# Charging.net
KiCad netlist of a schematic drawn in Altium Designer
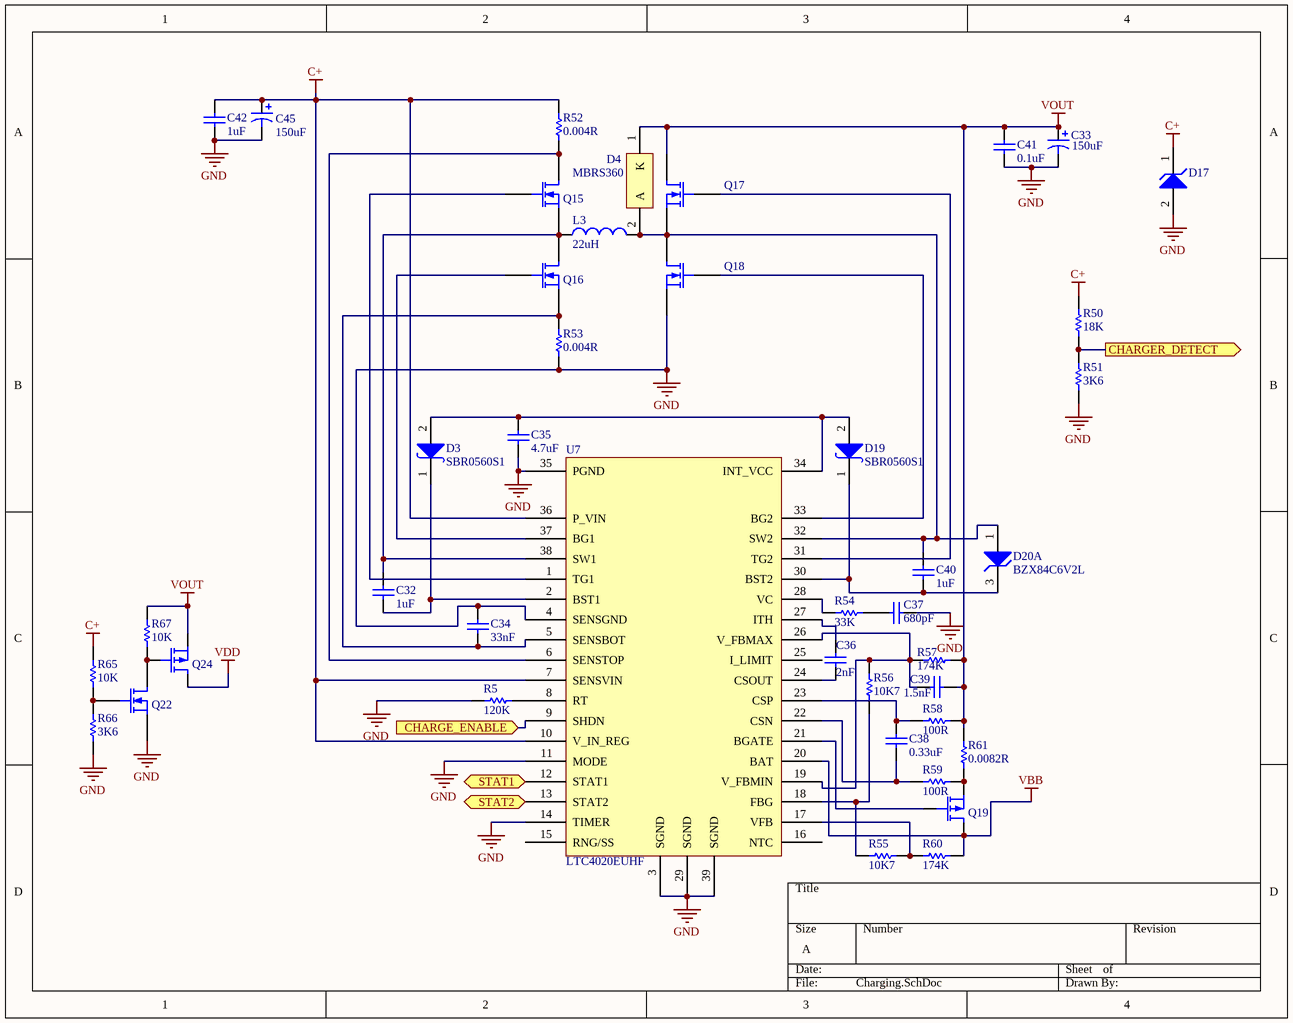
[diagram p0: Charging.SchDoc]

(export (version "E")
  (design (tool "Eeschema 10.0.6"))
  (components
    (comp (ref "C32")
      (value "1uF")
      (footprint "CAPC0603(1608)100_L")
      (description "CAP 1uF 25V Â±10% 0603 (1608 Metric) Thickness 1mm SMD")
      (fields (field (name "TOLERANCE") "Â±10%"))
      (libsource (lib "Altium Content Vault") (part "CAP"))
    )
    (comp (ref "C33")
      (value "150uF")
      (footprint "CAP 180uF 50V")
      (description "Polarized Capacitor (Axial)")
      (fields (field (name "PUBLISHER") "Altium Limited"))
      (libsource (lib "Components") (part "CAP 180uF 50V"))
    )
    (comp (ref "C34")
      (value "33nF")
      (footprint "CAPC0603(1608)100_M")
      (description "CAP 33nF 25V Â±5% 0603 (1608 Metric) Thickness 1mm SMD")
      (fields (field (name "TOLERANCE") "Â±5%"))
      (libsource (lib "Altium Content Vault") (part "CAP"))
    )
    (comp (ref "C35")
      (value "4.7uF")
      (footprint "CAPC0603(1608)55_L")
      (description "CAP 4.7uF 6.3V Â±10% 0603 (1608 Metric) Thickness 0.55mm SMD")
      (fields (field (name "TOLERANCE") "Â±10%"))
      (libsource (lib "Altium Content Vault") (part "CMP-1035-02779-1"))
    )
    (comp (ref "C36")
      (value "2nF")
      (footprint "CAPC0603(1608)100_L")
      (description "CAP 2.2nF 6.3V Â±5% 0603 (1608 Metric) Thickness 1mm SMD")
      (fields (field (name "TOLERANCE") "Â±5%"))
      (libsource (lib "Altium Content Vault") (part "CAP"))
    )
    (comp (ref "C37")
      (value "680pF")
      (footprint "CAPC0603(1608)100_L")
      (description "CAP 680pF 6.3V Â±5% 0603 (1608 Metric) Thickness 1mm SMD")
      (fields (field (name "TOLERANCE") "Â±5%"))
      (libsource (lib "Altium Content Vault") (part "CAP"))
    )
    (comp (ref "C38")
      (value "0.33uF")
      (footprint "CAPC0603(1608)100_M")
      (description "CAP 330nF 50V Â±10% 0603 (1608 Metric) Thickness 1mm SMD")
      (fields (field (name "TOLERANCE") "Â±10%"))
      (libsource (lib "Altium Content Vault") (part "CAP"))
    )
    (comp (ref "C39")
      (value "1.5nF")
      (footprint "CAPC0603(1608)100_N")
      (description "CAP 1.5nF 6.3V Â±5% 0603 (1608 Metric) Thickness 1mm SMD")
      (fields (field (name "TOLERANCE") "Â±5%"))
      (libsource (lib "Altium Content Vault") (part "CAP"))
    )
    (comp (ref "C40")
      (value "1uF")
      (footprint "CAPC0603(1608)100_L")
      (description "CAP 1uF 25V Â±10% 0603 (1608 Metric) Thickness 1mm SMD")
      (fields (field (name "TOLERANCE") "Â±10%"))
      (libsource (lib "Altium Content Vault") (part "CAP"))
    )
    (comp (ref "C41")
      (value "0.1uF")
      (footprint "CAPC0603(1608)100_L")
      (description "CAP 100nF 50V Â±5% 0603 (1608 Metric) Thickness 1mm SMD")
      (fields (field (name "TOLERANCE") "Â±5%"))
      (libsource (lib "Altium Content Vault") (part "CMP-1035-02591-1"))
    )
    (comp (ref "C42")
      (value "1uF")
      (footprint "CAPC0603(1608)100_L")
      (description "CAP 1uF 25V Â±10% 0603 (1608 Metric) Thickness 1mm SMD")
      (fields (field (name "TOLERANCE") "Â±10%"))
      (libsource (lib "Altium Content Vault") (part "CAP"))
    )
    (comp (ref "C45")
      (value "150uF")
      (footprint "CAP 150uF 25V")
      (description "Polarized Capacitor (Axial)")
      (fields (field (name "PUBLISHER") "Altium Limited"))
      (libsource (lib "Components") (part "CAP 150uF 25V"))
    )
    (comp (ref "D3")
      (value "SBR0560S1")
      (footprint "SOD-123")
      (libsource (lib "Components") (part "SBR0560S1"))
    )
    (comp (ref "D4")
      (value "MBRS360")
      (footprint "ONSC-SMB-2-403A-03_H_V")
      (description "Schottky Power Rectifier, 2-Pin SMB, Pb-Free, Tape and Reel")
      (fields (field (name "MANUFACTURER") "On Semiconductor") (field (name "PARTNUMBER") "MBRS360BT3G"))
      (libsource (lib "Altium Content Vault") (part "ONSC-D-K1A2-2_A"))
    )
    (comp (ref "D17")
      (value "~")
      (footprint "ONSC-SOD-123-2-425-04_V")
      (description "Zener Voltage Regulator, 500 mW, 2-Pin SOD-123, Pb-Free, Tape and Reel")
      (fields (field (name "PARTNUMBER") "MMSZ24T1G") (field (name "MANUFACTURER") "On Semiconductor"))
      (libsource (lib "Altium Inc") (part "ONSC-K1A2-2"))
    )
    (comp (ref "D19")
      (value "SBR0560S1")
      (footprint "SOD-123")
      (libsource (lib "Components") (part "SBR0560S1"))
    )
    (comp (ref "D20")
      (value "BZX84C6V2L")
      (footprint "ONSC-SOT-23-3-318-08_V")
      (description "Zener Voltage Regulator, 225 mW, 3-Pin SOT-23, Pb-Free, Tape and Reel")
      (fields (field (name "MANUFACTURER") "On Semiconductor") (field (name "PARTNUMBER") "BZX84C6V2LT3G"))
      (libsource (lib "Altium Content Vault") (part "CMP-1060-00911-1"))
    )
    (comp (ref "L3")
      (value "22uH")
      (footprint "IHLP-6767GZ")
      (description "Inductor")
      (fields (field (name "PUBLISHER") "Altium Limited"))
      (libsource (lib "Components") (part "IHLP6767"))
    )
    (comp (ref "Q15")
      (value "MOSFET-N")
      (footprint "SOIC127P600X175-8N")
      (description "N-Channel MOSFET")
      (fields (field (name "PUBLISHER") "Altium Limited"))
      (libsource (lib "Components") (part "MOSFET-N"))
    )
    (comp (ref "Q16")
      (value "MOSFET-N")
      (footprint "SOIC127P600X175-8N")
      (description "N-Channel MOSFET")
      (fields (field (name "PUBLISHER") "Altium Limited"))
      (libsource (lib "Components") (part "MOSFET-N"))
    )
    (comp (ref "Q17")
      (value "MOSFET-N")
      (footprint "SOIC127P600X175-8N")
      (description "N-Channel MOSFET")
      (fields (field (name "PUBLISHER") "Altium Limited"))
      (libsource (lib "Components") (part "MOSFET-N"))
    )
    (comp (ref "Q18")
      (value "MOSFET-N")
      (footprint "SOIC127P600X175-8N")
      (description "N-Channel MOSFET")
      (fields (field (name "PUBLISHER") "Altium Limited"))
      (libsource (lib "Components") (part "MOSFET-N"))
    )
    (comp (ref "Q19")
      (value "MOSFET-P")
      (footprint "SOIC127P600X175-8N")
      (description "P-Channel MOSFET")
      (fields (field (name "PUBLISHER") "Altium Limited"))
      (libsource (lib "Components") (part "MOSFET-P"))
    )
    (comp (ref "Q22")
      (value "MOSFET-N")
      (footprint "SOT23-3")
      (description "N-Channel MOSFET")
      (fields (field (name "PUBLISHER") "Altium Limited"))
      (libsource (lib "Components") (part "MOSFET-N"))
    )
    (comp (ref "Q24")
      (value "MOSFET-P")
      (footprint "SOT23-3")
      (description "P-Channel MOSFET")
      (fields (field (name "PUBLISHER") "Altium Limited"))
      (libsource (lib "Components") (part "MOSFET-P"))
    )
    (comp (ref "R5")
      (value "120K")
      (footprint "RESC0603(1608)_L")
      (description "120K 0.1W 5% 0603 (1608 Metric)  SMD")
      (fields (field (name "POWER") "0.1 W") (field (name "TOLERANCE") "5 %"))
      (libsource (lib "Altium Content Vault") (part "CMP-1012-00124-1"))
    )
    (comp (ref "R50")
      (value "18K")
      (footprint "RESC0603(1608)_L")
      (description "18K 0.1W 1% 0603 (1608 Metric)  SMD")
      (fields (field (name "POWER") "0.1 W") (field (name "TOLERANCE") "1 %"))
      (libsource (lib "Altium Content Vault") (part "CMP-1012-00650-1"))
    )
    (comp (ref "R51")
      (value "3K6")
      (footprint "RESC0603(1608)_L")
      (description "3K6 0.1W 1% 0603 (1608 Metric)  SMD")
      (fields (field (name "TOLERANCE") "1 %") (field (name "POWER") "0.1 W"))
      (libsource (lib "Altium Content Vault") (part "RES"))
    )
    (comp (ref "R52")
      (value "0.004R")
      (footprint "RESC1206(3216)_L")
      (description "1R 0.25W 1% 1206 (3216 Metric)  SMD")
      (fields (field (name "POWER") "0.25 W") (field (name "TOLERANCE") "1 %"))
      (libsource (lib "Altium Content Vault") (part "RES"))
    )
    (comp (ref "R53")
      (value "0.004R")
      (footprint "RESC1206(3216)_L")
      (description "1R 0.25W 1% 1206 (3216 Metric)  SMD")
      (fields (field (name "POWER") "0.25 W") (field (name "TOLERANCE") "1 %"))
      (libsource (lib "Altium Content Vault") (part "RES"))
    )
    (comp (ref "R54")
      (value "33K")
      (footprint "RESC0603(1608)_N")
      (description "33K 0.1W 1% 0603 (1608 Metric)  SMD")
      (fields (field (name "TOLERANCE") "1 %") (field (name "POWER") "0.1 W"))
      (libsource (lib "Altium Content Vault") (part "RES"))
    )
    (comp (ref "R55")
      (value "10K7")
      (footprint "RESC0603(1608)_M")
      (description "110K 0.1W 5% 0603 (1608 Metric)  SMD")
      (fields (field (name "TOLERANCE") "5 %") (field (name "POWER") "0.1 W"))
      (libsource (lib "Altium Content Vault") (part "CMP-1012-00123-1"))
    )
    (comp (ref "R56")
      (value "10K7")
      (footprint "RESC0603(1608)_M")
      (description "110K 0.1W 5% 0603 (1608 Metric)  SMD")
      (fields (field (name "TOLERANCE") "5 %") (field (name "POWER") "0.1 W"))
      (libsource (lib "Altium Content Vault") (part "CMP-1012-00123-1"))
    )
    (comp (ref "R57")
      (value "174K")
      (footprint "RESC0603(1608)_L")
      (description "1M8 0.1W 5% 0603 (1608 Metric)  SMD")
      (fields (field (name "TOLERANCE") "5 %") (field (name "POWER") "0.1 W"))
      (libsource (lib "Altium Content Vault") (part "RES"))
    )
    (comp (ref "R58")
      (value "100R")
      (footprint "RESC0603(1608)_L")
      (description "100R 0.1W 5% 0603 (1608 Metric)  SMD")
      (fields (field (name "TOLERANCE") "5 %") (field (name "POWER") "0.1 W"))
      (libsource (lib "Altium Content Vault") (part "RES"))
    )
    (comp (ref "R59")
      (value "100R")
      (footprint "RESC0603(1608)_L")
      (description "100R 0.1W 5% 0603 (1608 Metric)  SMD")
      (fields (field (name "TOLERANCE") "5 %") (field (name "POWER") "0.1 W"))
      (libsource (lib "Altium Content Vault") (part "RES"))
    )
    (comp (ref "R60")
      (value "174K")
      (footprint "RESC0603(1608)_L")
      (description "1M8 0.1W 5% 0603 (1608 Metric)  SMD")
      (fields (field (name "TOLERANCE") "5 %") (field (name "POWER") "0.1 W"))
      (libsource (lib "Altium Content Vault") (part "CMP-1012-00152-1"))
    )
    (comp (ref "R61")
      (value "0.0082R")
      (footprint "RESC2010(5025)_M")
      (description "1R 0.75W 1% 2010 (5025 Metric)  SMD")
      (fields (field (name "TOLERANCE") "1 %") (field (name "POWER") "0.75 W"))
      (libsource (lib "Altium Content Vault") (part "CMP-1017-00171-1"))
    )
    (comp (ref "R65")
      (value "10K")
      (footprint "RESC0603(1608)_N")
      (description "10K 0.1W 5% 0603 (1608 Metric)  SMD")
      (fields (field (name "TOLERANCE") "5 %") (field (name "POWER") "0.1 W"))
      (libsource (lib "Altium Content Vault") (part "RES"))
    )
    (comp (ref "R66")
      (value "3K6")
      (footprint "RESC0603(1608)_N")
      (description "3K6 0.1W 5% 0603 (1608 Metric)  SMD")
      (fields (field (name "POWER") "0.1 W") (field (name "TOLERANCE") "5 %"))
      (libsource (lib "Altium Content Vault") (part "RES"))
    )
    (comp (ref "R67")
      (value "10K")
      (footprint "RESC0603(1608)_N")
      (description "10K 0.1W 5% 0603 (1608 Metric)  SMD")
      (fields (field (name "TOLERANCE") "5 %") (field (name "POWER") "0.1 W"))
      (libsource (lib "Altium Content Vault") (part "RES"))
    )
    (comp (ref "U7")
      (value "LTC4020EUHF")
      (footprint "QFN38")
      (libsource (lib "Components") (part "LTC4020EUHF"))
    )
  )
  (nets
    (net (code "1") (name "/CHARGER_DETECT") (class "Default")
      (node (ref "R50") (pin "1") (pinfunction "1_1") (pintype "passive"))
      (node (ref "R51") (pin "2") (pinfunction "2_2") (pintype "passive"))
    )
    (net (code "2") (name "/CHARGE_ENABLE") (class "Default")
      (node (ref "U7") (pin "9") (pinfunction "SHDN_9") (pintype "passive"))
    )
    (net (code "3") (name "/STAT1") (class "Default")
      (node (ref "U7") (pin "12") (pinfunction "STAT1_12") (pintype "passive"))
    )
    (net (code "4") (name "/STAT2") (class "Default")
      (node (ref "U7") (pin "13") (pinfunction "STAT2_13") (pintype "passive"))
    )
    (net (code "5") (name "C+") (class "Default")
      (node (ref "C42") (pin "2") (pinfunction "2_2") (pintype "passive"))
      (node (ref "C45") (pin "1") (pinfunction "1_1") (pintype "passive"))
      (node (ref "D17") (pin "1") (pinfunction "K_1") (pintype "passive"))
      (node (ref "R50") (pin "2") (pinfunction "2_2") (pintype "passive"))
      (node (ref "R52") (pin "2") (pinfunction "2_2") (pintype "passive"))
      (node (ref "R65") (pin "2") (pinfunction "2_2") (pintype "passive"))
      (node (ref "U7") (pin "10") (pinfunction "V_IN_REG_10") (pintype "passive"))
      (node (ref "U7") (pin "36") (pinfunction "P_VIN_36") (pintype "passive"))
      (node (ref "U7") (pin "7") (pinfunction "SENSVIN_7") (pintype "passive"))
    )
    (net (code "6") (name "GND") (class "Default")
      (node (ref "C33") (pin "2") (pinfunction "2_2") (pintype "passive"))
      (node (ref "C34") (pin "2") (pinfunction "2_2") (pintype "passive"))
      (node (ref "C35") (pin "1") (pinfunction "1_1") (pintype "passive"))
      (node (ref "C37") (pin "2") (pinfunction "2_2") (pintype "passive"))
      (node (ref "C41") (pin "1") (pinfunction "1_1") (pintype "passive"))
      (node (ref "C42") (pin "1") (pinfunction "1_1") (pintype "passive"))
      (node (ref "C45") (pin "2") (pinfunction "2_2") (pintype "passive"))
      (node (ref "D17") (pin "2") (pinfunction "A_2") (pintype "passive"))
      (node (ref "Q18") (pin "3") (pinfunction "S_3") (pintype "passive"))
      (node (ref "Q22") (pin "3") (pinfunction "S_3") (pintype "passive"))
      (node (ref "R5") (pin "2") (pinfunction "2_2") (pintype "passive"))
      (node (ref "R51") (pin "1") (pinfunction "1_1") (pintype "passive"))
      (node (ref "R53") (pin "1") (pinfunction "1_1") (pintype "passive"))
      (node (ref "R66") (pin "1") (pinfunction "1_1") (pintype "passive"))
      (node (ref "U7") (pin "11") (pinfunction "MODE_11") (pintype "passive"))
      (node (ref "U7") (pin "14") (pinfunction "TIMER_14") (pintype "passive"))
      (node (ref "U7") (pin "29") (pinfunction "SGND_29") (pintype "passive"))
      (node (ref "U7") (pin "3") (pinfunction "SGND_3") (pintype "passive"))
      (node (ref "U7") (pin "35") (pinfunction "PGND_35") (pintype "passive"))
      (node (ref "U7") (pin "39") (pinfunction "SGND_39") (pintype "passive"))
      (node (ref "U7") (pin "4") (pinfunction "SENSGND_4") (pintype "passive"))
    )
    (net (code "7") (name "Net-(C37-Pad1)") (class "Default")
      (node (ref "C37") (pin "1") (pinfunction "1_1") (pintype "passive"))
      (node (ref "R54") (pin "2") (pinfunction "2_2") (pintype "passive"))
    )
    (net (code "8") (name "Net-(D3-K)") (class "Default")
      (node (ref "C32") (pin "1") (pinfunction "1_1") (pintype "passive"))
      (node (ref "D3") (pin "1") (pinfunction "K_1") (pintype "passive"))
      (node (ref "U7") (pin "2") (pinfunction "BST1_2") (pintype "passive"))
    )
    (net (code "9") (name "Net-(D19-A)") (class "Default")
      (node (ref "C35") (pin "2") (pinfunction "2_2") (pintype "passive"))
      (node (ref "D19") (pin "2") (pinfunction "A_2") (pintype "passive"))
      (node (ref "D3") (pin "2") (pinfunction "A_2") (pintype "passive"))
      (node (ref "U7") (pin "34") (pinfunction "INT_VCC_34") (pintype "passive"))
    )
    (net (code "10") (name "Net-(D19-K)") (class "Default")
      (node (ref "C40") (pin "1") (pinfunction "1_1") (pintype "passive"))
      (node (ref "D19") (pin "1") (pinfunction "K_1") (pintype "passive"))
      (node (ref "D20") (pin "3") (pinfunction "K_3") (pintype "passive"))
      (node (ref "U7") (pin "30") (pinfunction "BST2_30") (pintype "passive"))
    )
    (net (code "11") (name "Net-(D20A-A)") (class "Default")
      (node (ref "C40") (pin "2") (pinfunction "2_2") (pintype "passive"))
      (node (ref "D20") (pin "1") (pinfunction "A_1") (pintype "passive"))
      (node (ref "D4") (pin "2") (pinfunction "A_2") (pintype "passive"))
      (node (ref "L3") (pin "2") (pinfunction "2_2") (pintype "passive"))
      (node (ref "Q17") (pin "3") (pinfunction "S_3") (pintype "passive"))
      (node (ref "Q18") (pin "2") (pinfunction "D_2") (pintype "passive"))
      (node (ref "U7") (pin "32") (pinfunction "SW2_32") (pintype "passive"))
    )
    (net (code "12") (name "Net-(Q15-D)") (class "Default")
      (node (ref "Q15") (pin "2") (pinfunction "D_2") (pintype "passive"))
      (node (ref "R52") (pin "1") (pinfunction "1_1") (pintype "passive"))
      (node (ref "U7") (pin "6") (pinfunction "SENSTOP_6") (pintype "passive"))
    )
    (net (code "13") (name "Net-(Q15-G)") (class "Default")
      (node (ref "Q15") (pin "1") (pinfunction "G_1") (pintype "passive"))
      (node (ref "U7") (pin "1") (pinfunction "TG1_1") (pintype "passive"))
    )
    (net (code "14") (name "Net-(Q15-S)") (class "Default")
      (node (ref "C32") (pin "2") (pinfunction "2_2") (pintype "passive"))
      (node (ref "L3") (pin "1") (pinfunction "1_1") (pintype "passive"))
      (node (ref "Q15") (pin "3") (pinfunction "S_3") (pintype "passive"))
      (node (ref "Q16") (pin "2") (pinfunction "D_2") (pintype "passive"))
      (node (ref "U7") (pin "38") (pinfunction "SW1_38") (pintype "passive"))
    )
    (net (code "15") (name "Net-(Q16-G)") (class "Default")
      (node (ref "Q16") (pin "1") (pinfunction "G_1") (pintype "passive"))
      (node (ref "U7") (pin "37") (pinfunction "BG1_37") (pintype "passive"))
    )
    (net (code "16") (name "Net-(Q16-S)") (class "Default")
      (node (ref "C34") (pin "1") (pinfunction "1_1") (pintype "passive"))
      (node (ref "Q16") (pin "3") (pinfunction "S_3") (pintype "passive"))
      (node (ref "R53") (pin "2") (pinfunction "2_2") (pintype "passive"))
      (node (ref "U7") (pin "5") (pinfunction "SENSBOT_5") (pintype "passive"))
    )
    (net (code "17") (name "Net-(Q17-G)") (class "Default")
      (node (ref "Q17") (pin "1") (pinfunction "G_1") (pintype "passive"))
      (node (ref "U7") (pin "31") (pinfunction "TG2_31") (pintype "passive"))
    )
    (net (code "18") (name "Net-(Q18-G)") (class "Default")
      (node (ref "Q18") (pin "1") (pinfunction "G_1") (pintype "passive"))
      (node (ref "U7") (pin "33") (pinfunction "BG2_33") (pintype "passive"))
    )
    (net (code "19") (name "Net-(Q19-G)") (class "Default")
      (node (ref "Q19") (pin "1") (pinfunction "G_1") (pintype "passive"))
      (node (ref "U7") (pin "21") (pinfunction "BGATE_21") (pintype "passive"))
    )
    (net (code "20") (name "Net-(Q19-S)") (class "Default")
      (node (ref "Q19") (pin "3") (pinfunction "S_3") (pintype "passive"))
      (node (ref "R59") (pin "2") (pinfunction "2_2") (pintype "passive"))
      (node (ref "R61") (pin "1") (pinfunction "1_1") (pintype "passive"))
    )
    (net (code "21") (name "Net-(Q22-D)") (class "Default")
      (node (ref "Q22") (pin "2") (pinfunction "D_2") (pintype "passive"))
      (node (ref "Q24") (pin "1") (pinfunction "G_1") (pintype "passive"))
      (node (ref "R67") (pin "1") (pinfunction "1_1") (pintype "passive"))
    )
    (net (code "22") (name "Net-(Q22-G)") (class "Default")
      (node (ref "Q22") (pin "1") (pinfunction "G_1") (pintype "passive"))
      (node (ref "R65") (pin "1") (pinfunction "1_1") (pintype "passive"))
      (node (ref "R66") (pin "2") (pinfunction "2_2") (pintype "passive"))
    )
    (net (code "23") (name "Net-(U7-CSN)") (class "Default")
      (node (ref "C38") (pin "1") (pinfunction "1_1") (pintype "passive"))
      (node (ref "R59") (pin "1") (pinfunction "1_1") (pintype "passive"))
      (node (ref "U7") (pin "22") (pinfunction "CSN_22") (pintype "passive"))
    )
    (net (code "24") (name "Net-(U7-CSOUT)") (class "Default")
      (node (ref "C36") (pin "1") (pinfunction "1_1") (pintype "passive"))
      (node (ref "U7") (pin "24") (pinfunction "CSOUT_24") (pintype "passive"))
    )
    (net (code "25") (name "Net-(U7-CSP)") (class "Default")
      (node (ref "C38") (pin "2") (pinfunction "2_2") (pintype "passive"))
      (node (ref "R58") (pin "1") (pinfunction "1_1") (pintype "passive"))
      (node (ref "U7") (pin "23") (pinfunction "CSP_23") (pintype "passive"))
    )
    (net (code "26") (name "Net-(U7-FBG)") (class "Default")
      (node (ref "R55") (pin "1") (pinfunction "1_1") (pintype "passive"))
      (node (ref "R56") (pin "1") (pinfunction "1_1") (pintype "passive"))
      (node (ref "U7") (pin "18") (pinfunction "FBG_18") (pintype "passive"))
    )
    (net (code "27") (name "Net-(U7-ITH)") (class "Default")
      (node (ref "C36") (pin "2") (pinfunction "2_2") (pintype "passive"))
      (node (ref "U7") (pin "27") (pinfunction "ITH_27") (pintype "passive"))
    )
    (net (code "28") (name "Net-(U7-RT)") (class "Default")
      (node (ref "R5") (pin "1") (pinfunction "1_1") (pintype "passive"))
      (node (ref "U7") (pin "8") (pinfunction "RT_8") (pintype "passive"))
    )
    (net (code "29") (name "Net-(U7-VC)") (class "Default")
      (node (ref "R54") (pin "1") (pinfunction "1_1") (pintype "passive"))
      (node (ref "U7") (pin "28") (pinfunction "VC_28") (pintype "passive"))
    )
    (net (code "30") (name "Net-(U7-VFB)") (class "Default")
      (node (ref "R55") (pin "2") (pinfunction "2_2") (pintype "passive"))
      (node (ref "R60") (pin "1") (pinfunction "1_1") (pintype "passive"))
      (node (ref "U7") (pin "17") (pinfunction "VFB_17") (pintype "passive"))
    )
    (net (code "31") (name "Net-(U7-V_FBMAX)") (class "Default")
      (node (ref "C39") (pin "1") (pinfunction "1_1") (pintype "passive"))
      (node (ref "R56") (pin "2") (pinfunction "2_2") (pintype "passive"))
      (node (ref "R57") (pin "1") (pinfunction "1_1") (pintype "passive"))
      (node (ref "U7") (pin "19") (pinfunction "V_FBMIN_19") (pintype "passive"))
      (node (ref "U7") (pin "26") (pinfunction "V_FBMAX_26") (pintype "passive"))
    )
    (net (code "32") (name "VBB") (class "Default")
      (node (ref "Q19") (pin "2") (pinfunction "D_2") (pintype "passive"))
      (node (ref "R60") (pin "2") (pinfunction "2_2") (pintype "passive"))
      (node (ref "U7") (pin "20") (pinfunction "BAT_20") (pintype "passive"))
    )
    (net (code "33") (name "VDD") (class "Default")
      (node (ref "Q24") (pin "2") (pinfunction "D_2") (pintype "passive"))
    )
    (net (code "34") (name "VOUT") (class "Default")
      (node (ref "C33") (pin "1") (pinfunction "1_1") (pintype "passive"))
      (node (ref "C39") (pin "2") (pinfunction "2_2") (pintype "passive"))
      (node (ref "C41") (pin "2") (pinfunction "2_2") (pintype "passive"))
      (node (ref "D4") (pin "1") (pinfunction "K_1") (pintype "passive"))
      (node (ref "Q17") (pin "2") (pinfunction "D_2") (pintype "passive"))
      (node (ref "Q24") (pin "3") (pinfunction "S_3") (pintype "passive"))
      (node (ref "R57") (pin "2") (pinfunction "2_2") (pintype "passive"))
      (node (ref "R58") (pin "2") (pinfunction "2_2") (pintype "passive"))
      (node (ref "R61") (pin "2") (pinfunction "2_2") (pintype "passive"))
      (node (ref "R67") (pin "2") (pinfunction "2_2") (pintype "passive"))
    )
    (net (code "35") (name "unconnected-(U7-I_LIMIT-Pad25)") (class "Default")
      (node (ref "U7") (pin "25") (pinfunction "I_LIMIT_25") (pintype "passive"))
    )
    (net (code "36") (name "unconnected-(U7-NTC-Pad16)") (class "Default")
      (node (ref "U7") (pin "16") (pinfunction "NTC_16") (pintype "passive"))
    )
    (net (code "37") (name "unconnected-(U7-RNG{slash}SS-Pad15)") (class "Default")
      (node (ref "U7") (pin "15") (pinfunction "RNG/SS_15") (pintype "passive"))
    )
  )
)
